# Input_filter.net
KiCad netlist of a schematic drawn in Altium Designer
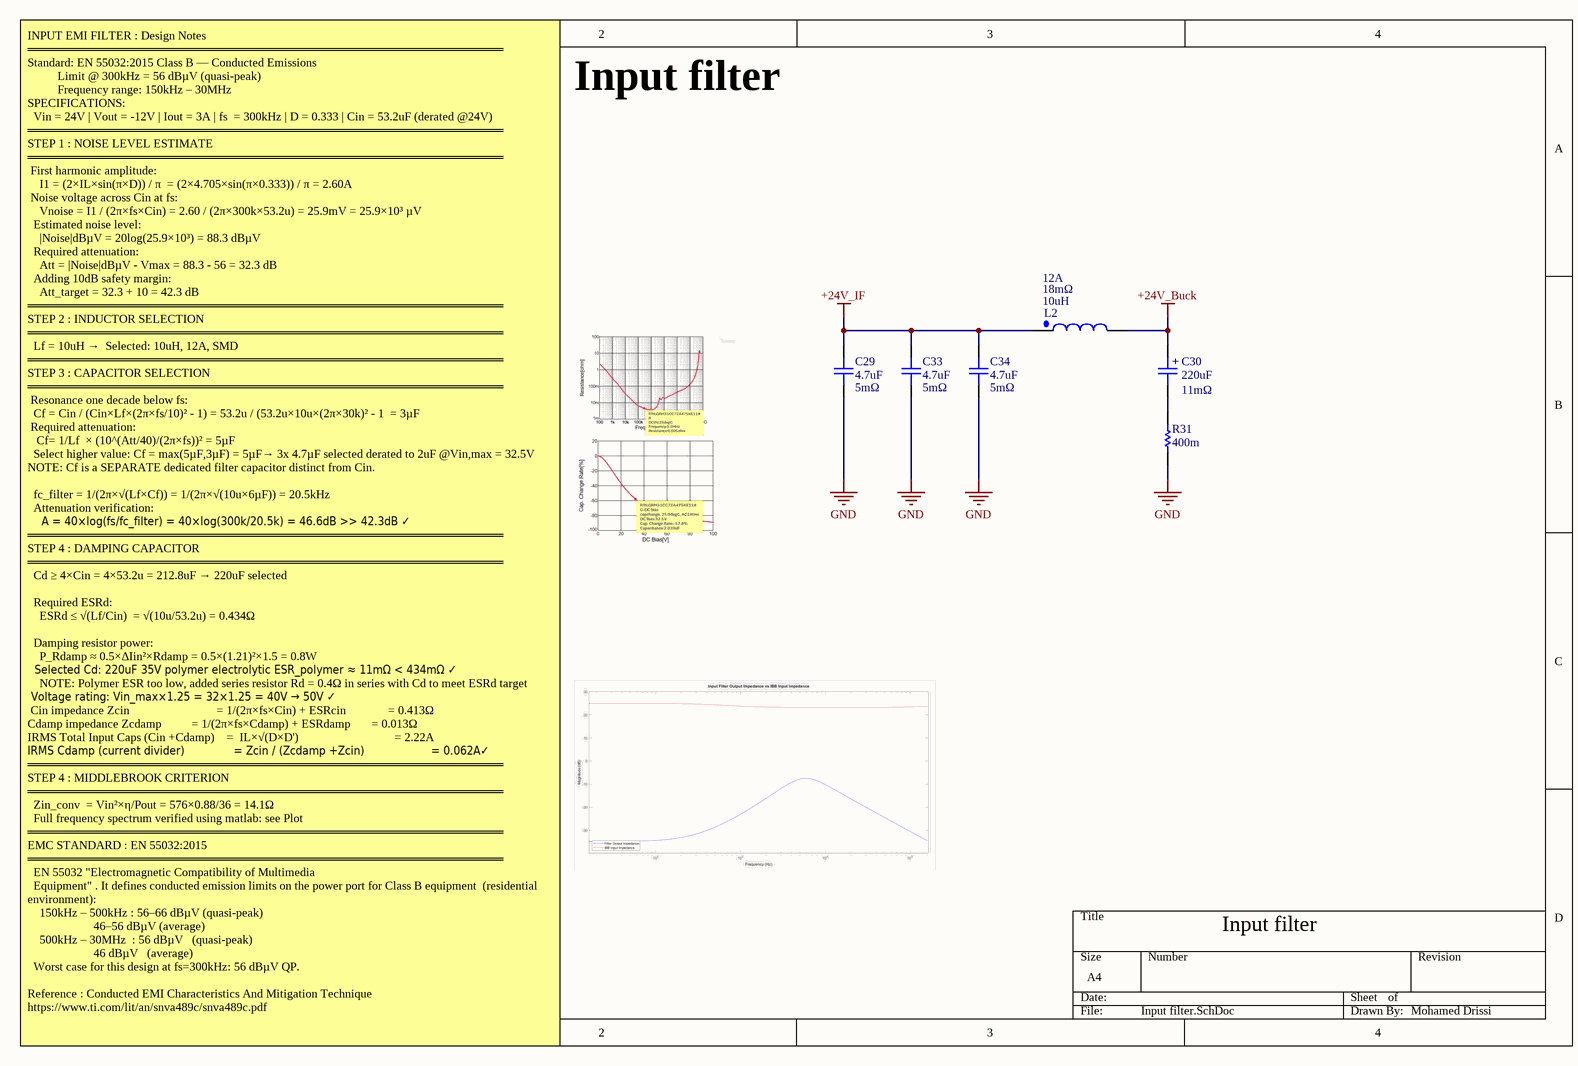
[diagram p0: Input filter.SchDoc]

(export (version "E")
  (design (tool "Eeschema 10.0.6"))
  (components
    (comp (ref "C29")
      (value "GRM31CC72A475KE11")
      (footprint "cap_1206")
      (description "100V 4.7uF X7S ±10% 1206 Multilayer Ceramic Capacitors MLCC - SMD/SMT ROHS")
      (fields
        (field (name "MANUFACTURER") "Murata")
        (field (name "MANUFACTURER PART NUMBER") "GRM31CC72A475KE11L")
        (field (name "CAPACITANCE") "4.7uF")
        (field (name "ESR") "5mΩ")
      )
      (libsource (lib "Inverting buck boost") (part "Murata GRM31CC72A475KE11L"))
    )
    (comp (ref "C30")
      (value "A786MW227M1HLAS011")
      (footprint "CAP_POL_10×16.5")
      (description "Cap, Alu Elec, Hybrid, 220Uf, 50V, Smd Rohs Compliant: Yes ¦Kemet A786MW227M1HLAS011")
      (fields
        (field (name "MANUFACTURER") "Yageo Group")
        (field (name "ESR (EQUIVALENT SERIES RESISTANCE)") "11mΩ")
        (field (name "CAPACITANCE") "220uF")
      )
      (libsource (lib "Inverting buck boost") (part "Kemet A786MW227M1HLAS011"))
    )
    (comp (ref "C33")
      (value "GRM31CC72A475KE11")
      (footprint "cap_1206")
      (description "100V 4.7uF X7S ±10% 1206 Multilayer Ceramic Capacitors MLCC - SMD/SMT ROHS")
      (fields
        (field (name "MANUFACTURER") "Murata")
        (field (name "MANUFACTURER PART NUMBER") "GRM31CC72A475KE11L")
        (field (name "CAPACITANCE") "4.7uF")
        (field (name "ESR") "5mΩ")
      )
      (libsource (lib "Inverting buck boost") (part "Murata GRM31CC72A475KE11L"))
    )
    (comp (ref "C34")
      (value "GRM31CC72A475KE11")
      (footprint "cap_1206")
      (description "100V 4.7uF X7S ±10% 1206 Multilayer Ceramic Capacitors MLCC - SMD/SMT ROHS")
      (fields
        (field (name "MANUFACTURER") "Murata")
        (field (name "MANUFACTURER PART NUMBER") "GRM31CC72A475KE11L")
        (field (name "CAPACITANCE") "4.7uF")
        (field (name "ESR") "5mΩ")
      )
      (libsource (lib "Inverting buck boost") (part "Murata GRM31CC72A475KE11L"))
    )
    (comp (ref "L2")
      (value "SRP1265CC-100M")
      (footprint "INDPM135125X650N")
      (description "Inductor Power Shielded Wirewound 10uH 20% 100KHz 20Q-FactorCarbonyl Powder 12A 0.018Ohm DCR T/R")
      (fields
        (field (name "MANUFACTURER") "Bourns")
        (field (name "DC RESISTANCE (DCR)") "18mΩ")
        (field (name "MAX CURRENT RATING") "12A")
        (field (name "TOLERANCE") "20%")
        (field (name "INDUCTANCE") "10uH")
      )
      (libsource (lib "Inverting buck boost") (part "Bourns SRP1265CC-100M"))
    )
    (comp (ref "R31")
      (value "MFHA1206R4000FC")
      (footprint "res_1206")
      (description "Res Metal Film 1206 0.4 Ohm 1% 1W ±100ppm/C Pad SMD T/R Automotive AEC-Q200")
      (fields
        (field (name "MANUFACTURER") "Eaton")
        (field (name "TOLERANCE") "1%")
        (field (name "RESISTANCE") "400m")
      )
      (libsource (lib "Inverting buck boost") (part "Eaton MFHA1206R4000FC"))
    )
  )
  (nets
    (net (code "1") (name "+24V_Buck") (class "Default")
      (node (ref "C30") (pin "1") (pinfunction "1_1") (pintype "passive"))
      (node (ref "L2") (pin "2") (pinfunction "2_2") (pintype "passive"))
    )
    (net (code "2") (name "+24V_IF") (class "Default")
      (node (ref "C29") (pin "2") (pinfunction "2_2") (pintype "passive"))
      (node (ref "C33") (pin "2") (pinfunction "2_2") (pintype "passive"))
      (node (ref "C34") (pin "2") (pinfunction "2_2") (pintype "passive"))
      (node (ref "L2") (pin "1") (pinfunction "1_1") (pintype "passive"))
    )
    (net (code "3") (name "GND") (class "Default")
      (node (ref "C29") (pin "1") (pinfunction "1_1") (pintype "passive"))
      (node (ref "C33") (pin "1") (pinfunction "1_1") (pintype "passive"))
      (node (ref "C34") (pin "1") (pinfunction "1_1") (pintype "passive"))
      (node (ref "R31") (pin "1") (pinfunction "1_1") (pintype "passive"))
    )
    (net (code "4") (name "Net-(C30-Pad2)") (class "Default")
      (node (ref "C30") (pin "2") (pinfunction "2_2") (pintype "passive"))
      (node (ref "R31") (pin "2") (pinfunction "2_2") (pintype "passive"))
    )
  )
)
